# untitled.net
KiCad netlist of a schematic drawn in EAGLE
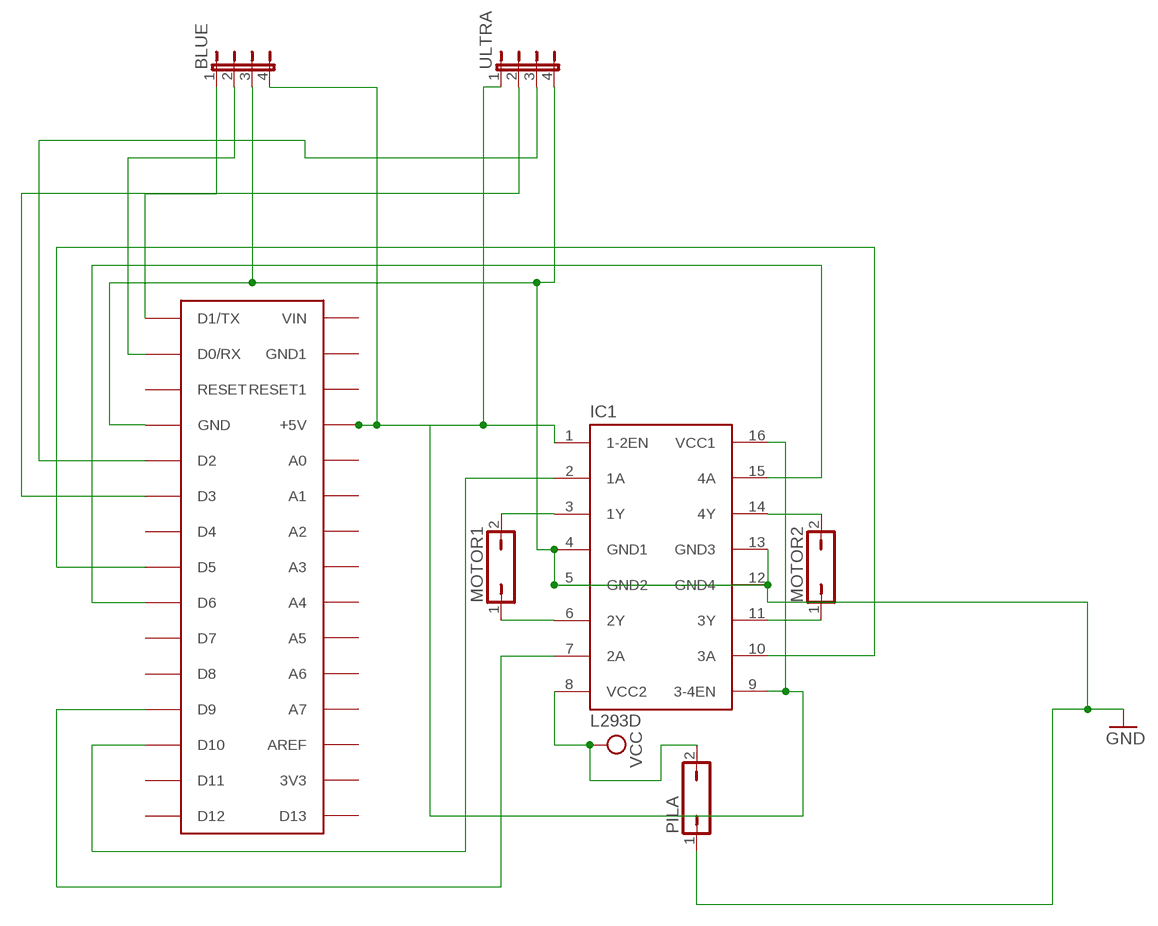
[diagram p0: schematic, sheet 1]

(export (version "E")
  (design (tool "Eeschema 10.0.6"))
  (components
    (comp (ref "BLUE")
      (value "JP4E")
      (footprint "eagle-import:JP4")
      (libsource (lib "eagle-import") (part "JP4E"))
    )
    (comp (ref "IC1")
      (value "L293D")
      (footprint "eagle-import:DIL16")
      (libsource (lib "eagle-import") (part "L293D"))
    )
    (comp (ref "MOTOR1")
      (value "JP1Q")
      (footprint "eagle-import:JP1")
      (libsource (lib "eagle-import") (part "JP1Q"))
    )
    (comp (ref "MOTOR2")
      (value "JP1Q")
      (footprint "eagle-import:JP1")
      (libsource (lib "eagle-import") (part "JP1Q"))
    )
    (comp (ref "PILA")
      (value "JP1Q")
      (footprint "eagle-import:JP1")
      (libsource (lib "eagle-import") (part "JP1Q"))
    )
    (comp (ref "U$1")
      (value "ARDUINONANO")
      (footprint "eagle-import:PDIP-32")
      (libsource (lib "eagle-import") (part "ARDUINONANO"))
    )
    (comp (ref "ULTRA")
      (value "JP4E")
      (footprint "eagle-import:JP4")
      (libsource (lib "eagle-import") (part "JP4E"))
    )
  )
  (nets
    (net (code "1") (name "GND") (class "Default")
      (node (ref "BLUE") (pin "3") (pinfunction "3_3") (pintype "passive"))
      (node (ref "IC1") (pin "12") (pinfunction "GND4_12") (pintype "power_in"))
      (node (ref "IC1") (pin "13") (pinfunction "GND3_13") (pintype "power_in"))
      (node (ref "IC1") (pin "4") (pinfunction "GND1_4") (pintype "power_in"))
      (node (ref "IC1") (pin "5") (pinfunction "GND2_5") (pintype "power_in"))
      (node (ref "PILA") (pin "1") (pinfunction "1_1") (pintype "passive"))
      (node (ref "U$1") (pin "GND") (pinfunction "GND_GND") (pintype "bidirectional"))
      (node (ref "ULTRA") (pin "4") (pinfunction "4_4") (pintype "passive"))
    )
    (net (code "2") (name "Net-(BLUE-Pad1)") (class "Default")
      (node (ref "BLUE") (pin "1") (pinfunction "1_1") (pintype "passive"))
      (node (ref "U$1") (pin "D1/TX") (pinfunction "D1/TX_D1/TX") (pintype "bidirectional"))
    )
    (net (code "3") (name "Net-(BLUE-Pad2)") (class "Default")
      (node (ref "BLUE") (pin "2") (pinfunction "2_2") (pintype "passive"))
      (node (ref "U$1") (pin "D0/RX") (pinfunction "D0/RX_D0/RX") (pintype "bidirectional"))
    )
    (net (code "4") (name "Net-(IC1-1-2EN)") (class "Default")
      (node (ref "BLUE") (pin "4") (pinfunction "4_4") (pintype "passive"))
      (node (ref "IC1") (pin "1") (pinfunction "1-2EN_1") (pintype "input"))
      (node (ref "IC1") (pin "16") (pinfunction "VCC1_16") (pintype "power_in"))
      (node (ref "IC1") (pin "9") (pinfunction "3-4EN_9") (pintype "input"))
      (node (ref "U$1") (pin "+5V") (pinfunction "+5V_+5V") (pintype "bidirectional"))
      (node (ref "ULTRA") (pin "1") (pinfunction "1_1") (pintype "passive"))
    )
    (net (code "5") (name "Net-(IC1-1A)") (class "Default")
      (node (ref "IC1") (pin "2") (pinfunction "1A_2") (pintype "input"))
      (node (ref "U$1") (pin "D10") (pinfunction "D10_D10") (pintype "bidirectional"))
    )
    (net (code "6") (name "Net-(IC1-1Y)") (class "Default")
      (node (ref "IC1") (pin "3") (pinfunction "1Y_3") (pintype "output"))
      (node (ref "MOTOR1") (pin "2") (pinfunction "2_2") (pintype "passive"))
    )
    (net (code "7") (name "Net-(IC1-2A)") (class "Default")
      (node (ref "IC1") (pin "7") (pinfunction "2A_7") (pintype "input"))
      (node (ref "U$1") (pin "D9") (pinfunction "D9_D9") (pintype "bidirectional"))
    )
    (net (code "8") (name "Net-(IC1-2Y)") (class "Default")
      (node (ref "IC1") (pin "6") (pinfunction "2Y_6") (pintype "output"))
      (node (ref "MOTOR1") (pin "1") (pinfunction "1_1") (pintype "passive"))
    )
    (net (code "9") (name "Net-(IC1-3A)") (class "Default")
      (node (ref "IC1") (pin "10") (pinfunction "3A_10") (pintype "input"))
      (node (ref "U$1") (pin "D5") (pinfunction "D5_D5") (pintype "bidirectional"))
    )
    (net (code "10") (name "Net-(IC1-3Y)") (class "Default")
      (node (ref "IC1") (pin "11") (pinfunction "3Y_11") (pintype "output"))
      (node (ref "MOTOR2") (pin "1") (pinfunction "1_1") (pintype "passive"))
    )
    (net (code "11") (name "Net-(IC1-4A)") (class "Default")
      (node (ref "IC1") (pin "15") (pinfunction "4A_15") (pintype "input"))
      (node (ref "U$1") (pin "D6") (pinfunction "D6_D6") (pintype "bidirectional"))
    )
    (net (code "12") (name "Net-(IC1-4Y)") (class "Default")
      (node (ref "IC1") (pin "14") (pinfunction "4Y_14") (pintype "output"))
      (node (ref "MOTOR2") (pin "2") (pinfunction "2_2") (pintype "passive"))
    )
    (net (code "13") (name "Net-(U$1-PadD2)") (class "Default")
      (node (ref "U$1") (pin "D2") (pinfunction "D2_D2") (pintype "bidirectional"))
      (node (ref "ULTRA") (pin "3") (pinfunction "3_3") (pintype "passive"))
    )
    (net (code "14") (name "Net-(U$1-PadD3)") (class "Default")
      (node (ref "U$1") (pin "D3") (pinfunction "D3_D3") (pintype "bidirectional"))
      (node (ref "ULTRA") (pin "2") (pinfunction "2_2") (pintype "passive"))
    )
    (net (code "15") (name "VCC") (class "Default")
      (node (ref "IC1") (pin "8") (pinfunction "VCC2_8") (pintype "power_in"))
      (node (ref "PILA") (pin "2") (pinfunction "2_2") (pintype "passive"))
    )
    (net (code "16") (name "unconnected-(U$1-Pad3V3)") (class "Default")
      (node (ref "U$1") (pin "3V3") (pinfunction "3V3_3V3") (pintype "bidirectional"))
    )
    (net (code "17") (name "unconnected-(U$1-PadA0)") (class "Default")
      (node (ref "U$1") (pin "A0") (pinfunction "A0_A0") (pintype "bidirectional"))
    )
    (net (code "18") (name "unconnected-(U$1-PadA1)") (class "Default")
      (node (ref "U$1") (pin "A1") (pinfunction "A1_A1") (pintype "bidirectional"))
    )
    (net (code "19") (name "unconnected-(U$1-PadA2)") (class "Default")
      (node (ref "U$1") (pin "A2") (pinfunction "A2_A2") (pintype "bidirectional"))
    )
    (net (code "20") (name "unconnected-(U$1-PadA3)") (class "Default")
      (node (ref "U$1") (pin "A3") (pinfunction "A3_A3") (pintype "bidirectional"))
    )
    (net (code "21") (name "unconnected-(U$1-PadA4)") (class "Default")
      (node (ref "U$1") (pin "A4") (pinfunction "A4_A4") (pintype "bidirectional"))
    )
    (net (code "22") (name "unconnected-(U$1-PadA5)") (class "Default")
      (node (ref "U$1") (pin "A5") (pinfunction "A5_A5") (pintype "bidirectional"))
    )
    (net (code "23") (name "unconnected-(U$1-PadA6)") (class "Default")
      (node (ref "U$1") (pin "A6") (pinfunction "A6_A6") (pintype "bidirectional"))
    )
    (net (code "24") (name "unconnected-(U$1-PadA7)") (class "Default")
      (node (ref "U$1") (pin "A7") (pinfunction "A7_A7") (pintype "bidirectional"))
    )
    (net (code "25") (name "unconnected-(U$1-PadAREF)") (class "Default")
      (node (ref "U$1") (pin "AREF") (pinfunction "AREF_AREF") (pintype "bidirectional"))
    )
    (net (code "26") (name "unconnected-(U$1-PadD4)") (class "Default")
      (node (ref "U$1") (pin "D4") (pinfunction "D4_D4") (pintype "bidirectional"))
    )
    (net (code "27") (name "unconnected-(U$1-PadD7)") (class "Default")
      (node (ref "U$1") (pin "D7") (pinfunction "D7_D7") (pintype "bidirectional"))
    )
    (net (code "28") (name "unconnected-(U$1-PadD8)") (class "Default")
      (node (ref "U$1") (pin "D8") (pinfunction "D8_D8") (pintype "bidirectional"))
    )
    (net (code "29") (name "unconnected-(U$1-PadD11)") (class "Default")
      (node (ref "U$1") (pin "D11") (pinfunction "D11_D11") (pintype "bidirectional"))
    )
    (net (code "30") (name "unconnected-(U$1-PadD12)") (class "Default")
      (node (ref "U$1") (pin "D12") (pinfunction "D12_D12") (pintype "bidirectional"))
    )
    (net (code "31") (name "unconnected-(U$1-PadD13)") (class "Default")
      (node (ref "U$1") (pin "D13") (pinfunction "D13_D13") (pintype "bidirectional"))
    )
    (net (code "32") (name "unconnected-(U$1-PadGND1)") (class "Default")
      (node (ref "U$1") (pin "GND1") (pinfunction "GND1_GND1") (pintype "bidirectional"))
    )
    (net (code "33") (name "unconnected-(U$1-PadRESET)") (class "Default")
      (node (ref "U$1") (pin "RESET") (pinfunction "RESET_RESET") (pintype "bidirectional"))
    )
    (net (code "34") (name "unconnected-(U$1-PadRESET1)") (class "Default")
      (node (ref "U$1") (pin "RESET1") (pinfunction "RESET1_RESET1") (pintype "bidirectional"))
    )
    (net (code "35") (name "unconnected-(U$1-PadVIN)") (class "Default")
      (node (ref "U$1") (pin "VIN") (pinfunction "VIN_VIN") (pintype "bidirectional"))
    )
  )
)
